# dc_dc_converter.net
KiCad netlist of a schematic drawn in Altium Designer
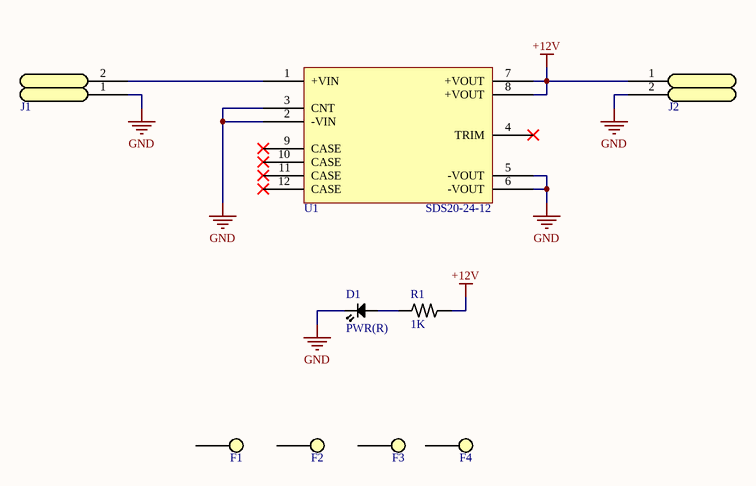
[diagram p0: dc_dc_converter.SchDoc]

(export (version "E")
  (design (tool "Eeschema 10.0.6"))
  (components
    (comp (ref "D1")
      (value "PWR(R)")
      (footprint "LED1608L")
      (description "Typical LED")
      (fields (field (name "Comment") "LED"))
      (libsource (lib "dc_dc_converter") (part "LED"))
    )
    (comp (ref "F1")
      (value "FIXED_HOLE")
      (footprint "FIXED_HOLE_PAD")
      (libsource (lib "dc_dc_converter") (part "FIXED_HOLE"))
    )
    (comp (ref "F2")
      (value "FIXED_HOLE")
      (footprint "FIXED_HOLE_PAD")
      (libsource (lib "dc_dc_converter") (part "FIXED_HOLE"))
    )
    (comp (ref "F3")
      (value "FIXED_HOLE")
      (footprint "FIXED_HOLE_PAD")
      (libsource (lib "dc_dc_converter") (part "FIXED_HOLE"))
    )
    (comp (ref "F4")
      (value "FIXED_HOLE")
      (footprint "FIXED_HOLE_PAD")
      (libsource (lib "dc_dc_converter") (part "FIXED_HOLE"))
    )
    (comp (ref "J1")
      (value "CON2")
      (footprint "DG128-5.0-02P")
      (description "Generic Connector 2 Pin")
      (libsource (lib "dc_dc_converter") (part "CON2"))
    )
    (comp (ref "J2")
      (value "CON2")
      (footprint "DG128-5.0-02P")
      (description "Generic Connector 2 Pin")
      (libsource (lib "dc_dc_converter") (part "CON2"))
    )
    (comp (ref "R1")
      (value "1K")
      (footprint "RES1608L")
      (description "Resistor")
      (fields (field (name "Comment") "R"))
      (libsource (lib "dc_dc_converter") (part "R"))
    )
    (comp (ref "U1")
      (value "SDS20-24-12")
      (footprint "SDS20-24-12")
      (libsource (lib "dc_dc_converter") (part "SDS20-24-12"))
    )
  )
  (nets
    (net (code "1") (name "+12V") (class "Default")
      (node (ref "J2") (pin "1") (pinfunction "1_1") (pintype "passive"))
      (node (ref "R1") (pin "2") (pinfunction "2_2") (pintype "passive"))
      (node (ref "U1") (pin "7") (pinfunction "+VOUT_7") (pintype "passive"))
      (node (ref "U1") (pin "8") (pinfunction "+VOUT_8") (pintype "passive"))
    )
    (net (code "2") (name "GND") (class "Default")
      (node (ref "D1") (pin "1") (pinfunction "1_1") (pintype "passive"))
      (node (ref "J1") (pin "1") (pinfunction "1_1") (pintype "passive"))
      (node (ref "J2") (pin "2") (pinfunction "2_2") (pintype "passive"))
      (node (ref "U1") (pin "2") (pinfunction "-VIN_2") (pintype "passive"))
      (node (ref "U1") (pin "3") (pinfunction "CNT_3") (pintype "passive"))
      (node (ref "U1") (pin "5") (pinfunction "-VOUT_5") (pintype "passive"))
      (node (ref "U1") (pin "6") (pinfunction "-VOUT_6") (pintype "passive"))
    )
    (net (code "3") (name "Net-(D1-Pad2)") (class "Default")
      (node (ref "D1") (pin "2") (pinfunction "2_2") (pintype "passive"))
      (node (ref "R1") (pin "1") (pinfunction "1_1") (pintype "passive"))
    )
    (net (code "4") (name "Net-(U1-+VIN)") (class "Default")
      (node (ref "J1") (pin "2") (pinfunction "2_2") (pintype "passive"))
      (node (ref "U1") (pin "1") (pinfunction "+VIN_1") (pintype "passive"))
    )
    (net (code "5") (name "unconnected-(F1-Pad1)") (class "Default")
      (node (ref "F1") (pin "1") (pinfunction "1_1") (pintype "passive"))
    )
    (net (code "6") (name "unconnected-(F2-Pad1)") (class "Default")
      (node (ref "F2") (pin "1") (pinfunction "1_1") (pintype "passive"))
    )
    (net (code "7") (name "unconnected-(F3-Pad1)") (class "Default")
      (node (ref "F3") (pin "1") (pinfunction "1_1") (pintype "passive"))
    )
    (net (code "8") (name "unconnected-(F4-Pad1)") (class "Default")
      (node (ref "F4") (pin "1") (pinfunction "1_1") (pintype "passive"))
    )
    (net (code "9") (name "unconnected-(U1-CASE-Pad9)") (class "Default")
      (node (ref "U1") (pin "9") (pinfunction "CASE_9") (pintype "passive+no_connect"))
    )
    (net (code "10") (name "unconnected-(U1-CASE-Pad10)") (class "Default")
      (node (ref "U1") (pin "10") (pinfunction "CASE_10") (pintype "passive+no_connect"))
    )
    (net (code "11") (name "unconnected-(U1-CASE-Pad11)") (class "Default")
      (node (ref "U1") (pin "11") (pinfunction "CASE_11") (pintype "passive+no_connect"))
    )
    (net (code "12") (name "unconnected-(U1-CASE-Pad12)") (class "Default")
      (node (ref "U1") (pin "12") (pinfunction "CASE_12") (pintype "passive+no_connect"))
    )
    (net (code "13") (name "unconnected-(U1-TRIM-Pad4)") (class "Default")
      (node (ref "U1") (pin "4") (pinfunction "TRIM_4") (pintype "passive+no_connect"))
    )
  )
)
